# untitled.net
KiCad netlist of a schematic drawn in EAGLE
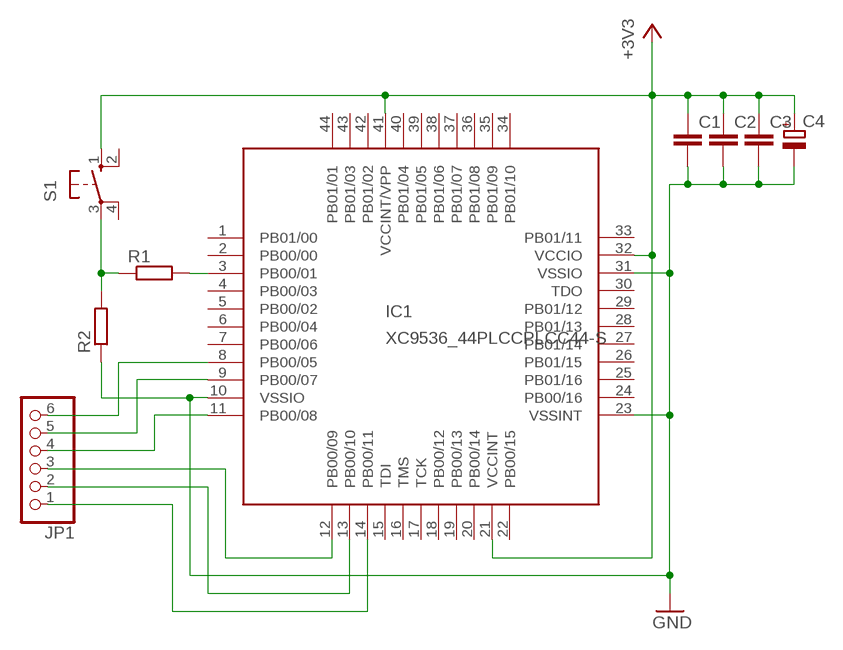
[diagram p0: schematic, sheet 1]

(export (version "E")
  (design (tool "Eeschema 10.0.6"))
  (components
    (comp (ref "C1")
      (value "C-EU050-025X075")
      (footprint "eagle-import:C050-025X075")
      (libsource (lib "eagle-import") (part "C-EU050-025X075"))
    )
    (comp (ref "C2")
      (value "C-EU050-025X075")
      (footprint "eagle-import:C050-025X075")
      (libsource (lib "eagle-import") (part "C-EU050-025X075"))
    )
    (comp (ref "C3")
      (value "C-EU050-025X075")
      (footprint "eagle-import:C050-025X075")
      (libsource (lib "eagle-import") (part "C-EU050-025X075"))
    )
    (comp (ref "C4")
      (value "CPOL-EUE2.5-6")
      (footprint "eagle-import:E2,5-6")
      (libsource (lib "eagle-import") (part "CPOL-EUE2.5-6"))
    )
    (comp (ref "IC1")
      (value "XC9536_44PLCCPLCC44-S")
      (footprint "eagle-import:PLCC-S44")
      (libsource (lib "eagle-import") (part "XC9536_44PLCCPLCC44-S"))
    )
    (comp (ref "JP1")
      (value "PINHD-1X6")
      (footprint "eagle-import:1X06")
      (libsource (lib "eagle-import") (part "PINHD-1X6"))
    )
    (comp (ref "R1")
      (value "R-EU_0204/7")
      (footprint "eagle-import:0204_7")
      (libsource (lib "eagle-import") (part "R-EU_0204/7"))
    )
    (comp (ref "R2")
      (value "R-EU_0204/7")
      (footprint "eagle-import:0204_7")
      (libsource (lib "eagle-import") (part "R-EU_0204/7"))
    )
    (comp (ref "S1")
      (value "10-XX")
      (footprint "eagle-import:B3F-10XX")
      (libsource (lib "eagle-import") (part "10-XX"))
    )
  )
  (nets
    (net (code "1") (name "+3V3") (class "Default")
      (node (ref "C1") (pin "1") (pinfunction "1_1") (pintype "passive"))
      (node (ref "C2") (pin "1") (pinfunction "1_1") (pintype "passive"))
      (node (ref "C3") (pin "1") (pinfunction "1_1") (pintype "passive"))
      (node (ref "C4") (pin "+") (pinfunction "+_+") (pintype "passive"))
      (node (ref "IC1") (pin "21") (pinfunction "VCCINT_21") (pintype "power_in"))
      (node (ref "IC1") (pin "32") (pinfunction "VCCIO_32") (pintype "power_in"))
      (node (ref "IC1") (pin "41") (pinfunction "VCCINT/VPP_41") (pintype "input"))
      (node (ref "S1") (pin "1") (pinfunction "S_1") (pintype "passive"))
    )
    (net (code "2") (name "GND") (class "Default")
      (node (ref "C1") (pin "2") (pinfunction "2_2") (pintype "passive"))
      (node (ref "C2") (pin "2") (pinfunction "2_2") (pintype "passive"))
      (node (ref "C3") (pin "2") (pinfunction "2_2") (pintype "passive"))
      (node (ref "C4") (pin "-") (pinfunction "-_-") (pintype "passive"))
      (node (ref "IC1") (pin "10") (pinfunction "VSSIO_10") (pintype "power_in"))
      (node (ref "IC1") (pin "23") (pinfunction "VSSINT_23") (pintype "power_in"))
      (node (ref "IC1") (pin "31") (pinfunction "VSSIO_31") (pintype "power_in"))
      (node (ref "R2") (pin "1") (pinfunction "1_1") (pintype "passive"))
    )
    (net (code "3") (name "Net-(IC1-PB00{slash}01)") (class "Default")
      (node (ref "IC1") (pin "3") (pinfunction "PB00/01_3") (pintype "bidirectional"))
      (node (ref "R1") (pin "2") (pinfunction "2_2") (pintype "passive"))
    )
    (net (code "4") (name "Net-(IC1-PB00{slash}05)") (class "Default")
      (node (ref "IC1") (pin "8") (pinfunction "PB00/05_8") (pintype "bidirectional"))
      (node (ref "JP1") (pin "6") (pinfunction "6_6") (pintype "passive"))
    )
    (net (code "5") (name "Net-(IC1-PB00{slash}07)") (class "Default")
      (node (ref "IC1") (pin "9") (pinfunction "PB00/07_9") (pintype "bidirectional"))
      (node (ref "JP1") (pin "5") (pinfunction "5_5") (pintype "passive"))
    )
    (net (code "6") (name "Net-(IC1-PB00{slash}08)") (class "Default")
      (node (ref "IC1") (pin "11") (pinfunction "PB00/08_11") (pintype "bidirectional"))
      (node (ref "JP1") (pin "4") (pinfunction "4_4") (pintype "passive"))
    )
    (net (code "7") (name "Net-(IC1-PB00{slash}09)") (class "Default")
      (node (ref "IC1") (pin "12") (pinfunction "PB00/09_12") (pintype "bidirectional"))
      (node (ref "JP1") (pin "3") (pinfunction "3_3") (pintype "passive"))
    )
    (net (code "8") (name "Net-(IC1-PB00{slash}10)") (class "Default")
      (node (ref "IC1") (pin "13") (pinfunction "PB00/10_13") (pintype "bidirectional"))
      (node (ref "JP1") (pin "2") (pinfunction "2_2") (pintype "passive"))
    )
    (net (code "9") (name "Net-(IC1-PB00{slash}11)") (class "Default")
      (node (ref "IC1") (pin "14") (pinfunction "PB00/11_14") (pintype "bidirectional"))
      (node (ref "JP1") (pin "1") (pinfunction "1_1") (pintype "passive"))
    )
    (net (code "10") (name "Net-(S1-P)") (class "Default")
      (node (ref "R1") (pin "1") (pinfunction "1_1") (pintype "passive"))
      (node (ref "R2") (pin "2") (pinfunction "2_2") (pintype "passive"))
      (node (ref "S1") (pin "3") (pinfunction "P_3") (pintype "passive"))
    )
    (net (code "11") (name "unconnected-(IC1-PB00{slash}00-Pad2)") (class "Default")
      (node (ref "IC1") (pin "2") (pinfunction "PB00/00_2") (pintype "bidirectional"))
    )
    (net (code "12") (name "unconnected-(IC1-PB00{slash}02-Pad5)") (class "Default")
      (node (ref "IC1") (pin "5") (pinfunction "PB00/02_5") (pintype "bidirectional"))
    )
    (net (code "13") (name "unconnected-(IC1-PB00{slash}03-Pad4)") (class "Default")
      (node (ref "IC1") (pin "4") (pinfunction "PB00/03_4") (pintype "bidirectional"))
    )
    (net (code "14") (name "unconnected-(IC1-PB00{slash}04-Pad6)") (class "Default")
      (node (ref "IC1") (pin "6") (pinfunction "PB00/04_6") (pintype "bidirectional"))
    )
    (net (code "15") (name "unconnected-(IC1-PB00{slash}06-Pad7)") (class "Default")
      (node (ref "IC1") (pin "7") (pinfunction "PB00/06_7") (pintype "bidirectional"))
    )
    (net (code "16") (name "unconnected-(IC1-PB00{slash}12-Pad18)") (class "Default")
      (node (ref "IC1") (pin "18") (pinfunction "PB00/12_18") (pintype "bidirectional"))
    )
    (net (code "17") (name "unconnected-(IC1-PB00{slash}13-Pad19)") (class "Default")
      (node (ref "IC1") (pin "19") (pinfunction "PB00/13_19") (pintype "bidirectional"))
    )
    (net (code "18") (name "unconnected-(IC1-PB00{slash}14-Pad20)") (class "Default")
      (node (ref "IC1") (pin "20") (pinfunction "PB00/14_20") (pintype "bidirectional"))
    )
    (net (code "19") (name "unconnected-(IC1-PB00{slash}15-Pad22)") (class "Default")
      (node (ref "IC1") (pin "22") (pinfunction "PB00/15_22") (pintype "bidirectional"))
    )
    (net (code "20") (name "unconnected-(IC1-PB00{slash}16-Pad24)") (class "Default")
      (node (ref "IC1") (pin "24") (pinfunction "PB00/16_24") (pintype "bidirectional"))
    )
    (net (code "21") (name "unconnected-(IC1-PB01{slash}00-Pad1)") (class "Default")
      (node (ref "IC1") (pin "1") (pinfunction "PB01/00_1") (pintype "bidirectional"))
    )
    (net (code "22") (name "unconnected-(IC1-PB01{slash}01-Pad44)") (class "Default")
      (node (ref "IC1") (pin "44") (pinfunction "PB01/01_44") (pintype "bidirectional"))
    )
    (net (code "23") (name "unconnected-(IC1-PB01{slash}02-Pad42)") (class "Default")
      (node (ref "IC1") (pin "42") (pinfunction "PB01/02_42") (pintype "bidirectional"))
    )
    (net (code "24") (name "unconnected-(IC1-PB01{slash}03-Pad43)") (class "Default")
      (node (ref "IC1") (pin "43") (pinfunction "PB01/03_43") (pintype "bidirectional"))
    )
    (net (code "25") (name "unconnected-(IC1-PB01{slash}04-Pad40)") (class "Default")
      (node (ref "IC1") (pin "40") (pinfunction "PB01/04_40") (pintype "bidirectional"))
    )
    (net (code "26") (name "unconnected-(IC1-PB01{slash}05-Pad39)") (class "Default")
      (node (ref "IC1") (pin "39") (pinfunction "PB01/05_39") (pintype "bidirectional"))
    )
    (net (code "27") (name "unconnected-(IC1-PB01{slash}06-Pad38)") (class "Default")
      (node (ref "IC1") (pin "38") (pinfunction "PB01/06_38") (pintype "bidirectional"))
    )
    (net (code "28") (name "unconnected-(IC1-PB01{slash}07-Pad37)") (class "Default")
      (node (ref "IC1") (pin "37") (pinfunction "PB01/07_37") (pintype "bidirectional"))
    )
    (net (code "29") (name "unconnected-(IC1-PB01{slash}08-Pad36)") (class "Default")
      (node (ref "IC1") (pin "36") (pinfunction "PB01/08_36") (pintype "bidirectional"))
    )
    (net (code "30") (name "unconnected-(IC1-PB01{slash}09-Pad35)") (class "Default")
      (node (ref "IC1") (pin "35") (pinfunction "PB01/09_35") (pintype "bidirectional"))
    )
    (net (code "31") (name "unconnected-(IC1-PB01{slash}10-Pad34)") (class "Default")
      (node (ref "IC1") (pin "34") (pinfunction "PB01/10_34") (pintype "bidirectional"))
    )
    (net (code "32") (name "unconnected-(IC1-PB01{slash}11-Pad33)") (class "Default")
      (node (ref "IC1") (pin "33") (pinfunction "PB01/11_33") (pintype "bidirectional"))
    )
    (net (code "33") (name "unconnected-(IC1-PB01{slash}12-Pad29)") (class "Default")
      (node (ref "IC1") (pin "29") (pinfunction "PB01/12_29") (pintype "bidirectional"))
    )
    (net (code "34") (name "unconnected-(IC1-PB01{slash}13-Pad28)") (class "Default")
      (node (ref "IC1") (pin "28") (pinfunction "PB01/13_28") (pintype "bidirectional"))
    )
    (net (code "35") (name "unconnected-(IC1-PB01{slash}14-Pad27)") (class "Default")
      (node (ref "IC1") (pin "27") (pinfunction "PB01/14_27") (pintype "bidirectional"))
    )
    (net (code "36") (name "unconnected-(IC1-PB01{slash}15-Pad26)") (class "Default")
      (node (ref "IC1") (pin "26") (pinfunction "PB01/15_26") (pintype "bidirectional"))
    )
    (net (code "37") (name "unconnected-(IC1-PB01{slash}16-Pad25)") (class "Default")
      (node (ref "IC1") (pin "25") (pinfunction "PB01/16_25") (pintype "bidirectional"))
    )
    (net (code "38") (name "unconnected-(IC1-TCK-Pad17)") (class "Default")
      (node (ref "IC1") (pin "17") (pinfunction "TCK_17") (pintype "input"))
    )
    (net (code "39") (name "unconnected-(IC1-TDI-Pad15)") (class "Default")
      (node (ref "IC1") (pin "15") (pinfunction "TDI_15") (pintype "input"))
    )
    (net (code "40") (name "unconnected-(IC1-TDO-Pad30)") (class "Default")
      (node (ref "IC1") (pin "30") (pinfunction "TDO_30") (pintype "output"))
    )
    (net (code "41") (name "unconnected-(IC1-TMS-Pad16)") (class "Default")
      (node (ref "IC1") (pin "16") (pinfunction "TMS_16") (pintype "input"))
    )
    (net (code "42") (name "unconnected-(S1-P1-Pad4)") (class "Default")
      (node (ref "S1") (pin "4") (pinfunction "P1_4") (pintype "passive"))
    )
    (net (code "43") (name "unconnected-(S1-S1-Pad2)") (class "Default")
      (node (ref "S1") (pin "2") (pinfunction "S1_2") (pintype "passive"))
    )
  )
)
